# PS_DC-DC_15V_24V.net
KiCad netlist of a schematic drawn in Altium Designer
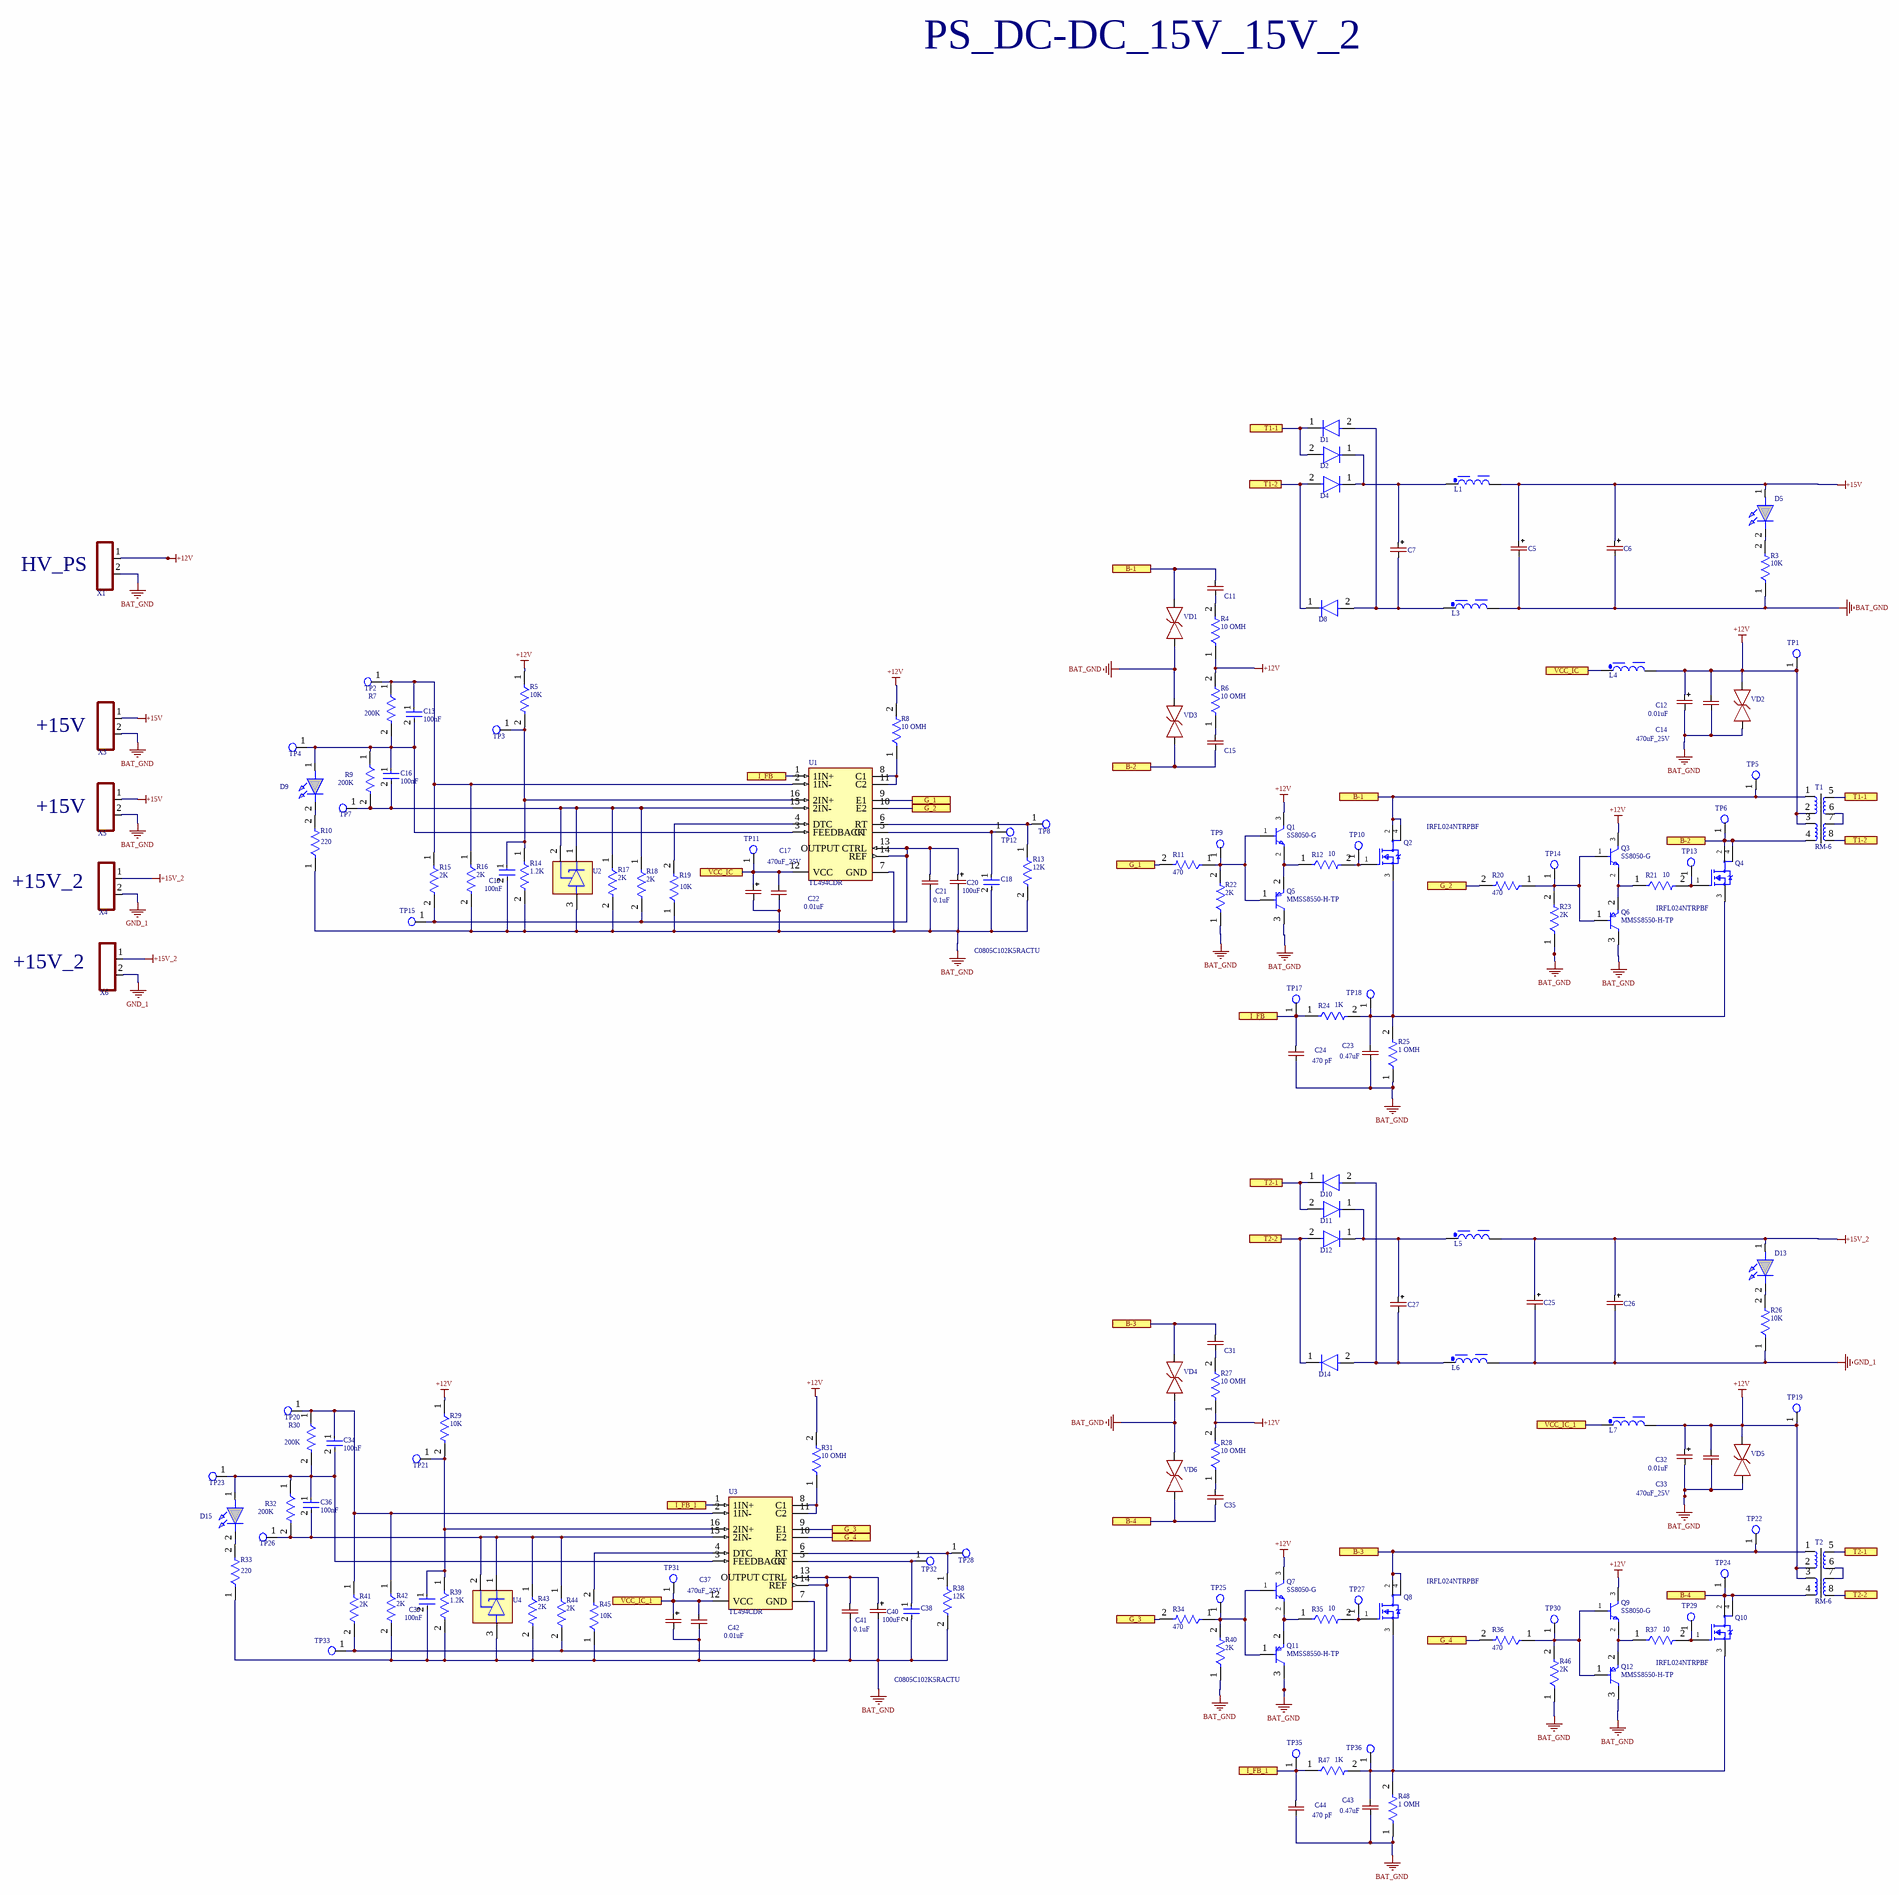
[diagram p0: PS_DC-DC_15V_24V.SchDoc]

(export (version "E")
  (design (tool "Eeschema 10.0.6"))
  (components
    (comp (ref "C5")
      (value "CAP-POLAR")
      (footprint "CAP_SMD_Size_G")
      (libsource (lib "PASSIVE_COMPONENTS") (part "CAP-POLAR"))
    )
    (comp (ref "C6")
      (value "CAP-POLAR")
      (footprint "CAP_SMD_Size_G")
      (libsource (lib "PASSIVE_COMPONENTS") (part "CAP-POLAR"))
    )
    (comp (ref "C7")
      (value "CAP-POLAR")
      (footprint "CAP_SMD_Size_G")
      (libsource (lib "PASSIVE_COMPONENTS") (part "CAP-POLAR"))
    )
    (comp (ref "C11")
      (value "CAP-V")
      (footprint "CAP-V")
      (libsource (lib "PASSIVE_COMPONENTS") (part "CAP-V"))
    )
    (comp (ref "C12")
      (value "0.01uF")
      (footprint "CAP-0805")
      (libsource (lib "PASSIVE_COMPONENTS") (part "CAP-NON-POLAR"))
    )
    (comp (ref "C13")
      (value "100nF")
      (footprint "FP-C0805C-DN-MFG")
      (description "CAP CER 10000PF 50V X7R 0805")
      (fields
        (field (name "MANUFACTURER PART NUMBER") "C0805C103J5RACTU")
        (field (name "MANUFACTURER") "KEMET")
      )
      (libsource (lib "Altium Content Vault") (part "b4654b650e69147ec39a6b967a45e02"))
    )
    (comp (ref "C14")
      (value "470uF_25V")
      (footprint "CAP_SMD_Size_G")
      (libsource (lib "PASSIVE_COMPONENTS") (part "CAP-POLAR"))
    )
    (comp (ref "C15")
      (value "CAP-V")
      (footprint "CAP-V")
      (libsource (lib "PASSIVE_COMPONENTS") (part "CAP-V"))
    )
    (comp (ref "C16")
      (value "100nF")
      (footprint "FP-C0805C-DN-MFG")
      (description "CAP CER 10000PF 50V X7R 0805")
      (fields
        (field (name "MANUFACTURER PART NUMBER") "C0805C103J5RACTU")
        (field (name "MANUFACTURER") "KEMET")
      )
      (libsource (lib "Altium Content Vault") (part "b4654b650e69147ec39a6b967a45e02"))
    )
    (comp (ref "C17")
      (value "470uF_25V")
      (footprint "CAP_SMD_Size_G")
      (libsource (lib "PASSIVE_COMPONENTS") (part "CAP-POLAR"))
    )
    (comp (ref "C18")
      (value "C0805C102K5RACTU")
      (footprint "FP-C0805C-DN-MFG")
      (description "CAP CER 1000PF 50V X7R 0805")
      (fields
        (field (name "OCTOPART") "https://octopart.com/c0805c102k5ractu-kemet-93010")
        (field (name "TOLERANCE") "0.1")
      )
      (libsource (lib "Altium Content Vault") (part "b4654b650e69147ec39a6b967a45e02"))
    )
    (comp (ref "C19")
      (value "100nF")
      (footprint "FP-C0805C-DN-MFG")
      (description "CAP CER 10000PF 50V X7R 0805")
      (fields
        (field (name "MANUFACTURER PART NUMBER") "C0805C103J5RACTU")
        (field (name "MANUFACTURER") "KEMET")
      )
      (libsource (lib "Altium Content Vault") (part "b4654b650e69147ec39a6b967a45e02"))
    )
    (comp (ref "C20")
      (value "100uF")
      (footprint "CAP-TAN-D")
      (libsource (lib "PASSIVE_COMPONENTS") (part "CAP-POLAR"))
    )
    (comp (ref "C21")
      (value "0.1uF")
      (footprint "CAP-0805")
      (libsource (lib "PASSIVE_COMPONENTS") (part "CAP-NON-POLAR"))
    )
    (comp (ref "C22")
      (value "0.01uF")
      (footprint "CAP-0805")
      (libsource (lib "PASSIVE_COMPONENTS") (part "CAP-NON-POLAR"))
    )
    (comp (ref "C23")
      (value "0.47uF")
      (footprint "CAP-0805")
      (libsource (lib "PASSIVE_COMPONENTS") (part "CAP-NON-POLAR"))
    )
    (comp (ref "C24")
      (value "470 pF")
      (footprint "CAP-0805")
      (libsource (lib "PASSIVE_COMPONENTS") (part "CAP-NON-POLAR"))
    )
    (comp (ref "C25")
      (value "CAP-POLAR")
      (footprint "CAP_SMD_Size_G")
      (libsource (lib "PASSIVE_COMPONENTS") (part "CAP-POLAR"))
    )
    (comp (ref "C26")
      (value "CAP-POLAR")
      (footprint "CAP_SMD_Size_G")
      (libsource (lib "PASSIVE_COMPONENTS") (part "CAP-POLAR"))
    )
    (comp (ref "C27")
      (value "CAP-POLAR")
      (footprint "CAP_SMD_Size_G")
      (libsource (lib "PASSIVE_COMPONENTS") (part "CAP-POLAR"))
    )
    (comp (ref "C31")
      (value "CAP-V")
      (footprint "CAP-V")
      (libsource (lib "PASSIVE_COMPONENTS") (part "CAP-V"))
    )
    (comp (ref "C32")
      (value "0.01uF")
      (footprint "CAP-0805")
      (libsource (lib "PASSIVE_COMPONENTS") (part "CAP-NON-POLAR"))
    )
    (comp (ref "C33")
      (value "470uF_25V")
      (footprint "CAP_SMD_Size_G")
      (libsource (lib "PASSIVE_COMPONENTS") (part "CAP-POLAR"))
    )
    (comp (ref "C34")
      (value "100nF")
      (footprint "FP-C0805C-DN-MFG")
      (description "CAP CER 10000PF 50V X7R 0805")
      (fields
        (field (name "MANUFACTURER PART NUMBER") "C0805C103J5RACTU")
        (field (name "MANUFACTURER") "KEMET")
      )
      (libsource (lib "Altium Content Vault") (part "b4654b650e69147ec39a6b967a45e02"))
    )
    (comp (ref "C35")
      (value "CAP-V")
      (footprint "CAP-V")
      (libsource (lib "PASSIVE_COMPONENTS") (part "CAP-V"))
    )
    (comp (ref "C36")
      (value "100nF")
      (footprint "FP-C0805C-DN-MFG")
      (description "CAP CER 10000PF 50V X7R 0805")
      (fields
        (field (name "MANUFACTURER PART NUMBER") "C0805C103J5RACTU")
        (field (name "MANUFACTURER") "KEMET")
      )
      (libsource (lib "Altium Content Vault") (part "b4654b650e69147ec39a6b967a45e02"))
    )
    (comp (ref "C37")
      (value "470uF_25V")
      (footprint "CAP_SMD_Size_G")
      (libsource (lib "PASSIVE_COMPONENTS") (part "CAP-POLAR"))
    )
    (comp (ref "C38")
      (value "C0805C102K5RACTU")
      (footprint "FP-C0805C-DN-MFG")
      (description "CAP CER 1000PF 50V X7R 0805")
      (fields
        (field (name "OCTOPART") "https://octopart.com/c0805c102k5ractu-kemet-93010")
        (field (name "TOLERANCE") "0.1")
      )
      (libsource (lib "Altium Content Vault") (part "b4654b650e69147ec39a6b967a45e02"))
    )
    (comp (ref "C39")
      (value "100nF")
      (footprint "FP-C0805C-DN-MFG")
      (description "CAP CER 10000PF 50V X7R 0805")
      (fields
        (field (name "MANUFACTURER PART NUMBER") "C0805C103J5RACTU")
        (field (name "MANUFACTURER") "KEMET")
      )
      (libsource (lib "Altium Content Vault") (part "b4654b650e69147ec39a6b967a45e02"))
    )
    (comp (ref "C40")
      (value "100uF")
      (footprint "CAP-TAN-D")
      (libsource (lib "PASSIVE_COMPONENTS") (part "CAP-POLAR"))
    )
    (comp (ref "C41")
      (value "0.1uF")
      (footprint "CAP-0805")
      (libsource (lib "PASSIVE_COMPONENTS") (part "CAP-NON-POLAR"))
    )
    (comp (ref "C42")
      (value "0.01uF")
      (footprint "CAP-0805")
      (libsource (lib "PASSIVE_COMPONENTS") (part "CAP-NON-POLAR"))
    )
    (comp (ref "C43")
      (value "0.47uF")
      (footprint "CAP-0805")
      (libsource (lib "PASSIVE_COMPONENTS") (part "CAP-NON-POLAR"))
    )
    (comp (ref "C44")
      (value "470 pF")
      (footprint "CAP-0805")
      (libsource (lib "PASSIVE_COMPONENTS") (part "CAP-NON-POLAR"))
    )
    (comp (ref "D1") (value "US1G") (footprint "DO-214AA") (libsource (lib "Diodes") (part "US1G")))
    (comp (ref "D2") (value "US1G") (footprint "DO-214AA") (libsource (lib "Diodes") (part "US1G")))
    (comp (ref "D4") (value "US1G") (footprint "DO-214AA") (libsource (lib "Diodes") (part "US1G")))
    (comp (ref "D5")
      (value "151031YS06000")
      (footprint "LED_RED")
      (description "WURTH ELEKTRONIK - 151031YS06000 - LED, Yellow, Through Hole, T-1 (3mm), 30 mA, 2 V, 590 nm")
      (fields (field (name "MOUSER PART NUMBER") "710-151031YS06000"))
      (libsource (lib "Optic-LED") (part "LED"))
    )
    (comp (ref "D8") (value "US1G") (footprint "DO-214AA") (libsource (lib "Diodes") (part "US1G")))
    (comp (ref "D9")
      (value "151031YS06000")
      (footprint "LED_RED")
      (description "WURTH ELEKTRONIK - 151031YS06000 - LED, Yellow, Through Hole, T-1 (3mm), 30 mA, 2 V, 590 nm")
      (fields (field (name "MOUSER PART NUMBER") "710-151031YS06000"))
      (libsource (lib "Optic-LED") (part "LED"))
    )
    (comp (ref "D10") (value "US1G") (footprint "DO-214AA") (libsource (lib "Diodes") (part "US1G")))
    (comp (ref "D11") (value "US1G") (footprint "DO-214AA") (libsource (lib "Diodes") (part "US1G")))
    (comp (ref "D12") (value "US1G") (footprint "DO-214AA") (libsource (lib "Diodes") (part "US1G")))
    (comp (ref "D13")
      (value "151031YS06000")
      (footprint "LED_RED")
      (description "WURTH ELEKTRONIK - 151031YS06000 - LED, Yellow, Through Hole, T-1 (3mm), 30 mA, 2 V, 590 nm")
      (fields (field (name "MOUSER PART NUMBER") "710-151031YS06000"))
      (libsource (lib "Optic-LED") (part "LED"))
    )
    (comp (ref "D14") (value "US1G") (footprint "DO-214AA") (libsource (lib "Diodes") (part "US1G")))
    (comp (ref "D15")
      (value "151031YS06000")
      (footprint "LED_RED")
      (description "WURTH ELEKTRONIK - 151031YS06000 - LED, Yellow, Through Hole, T-1 (3mm), 30 mA, 2 V, 590 nm")
      (fields (field (name "MOUSER PART NUMBER") "710-151031YS06000"))
      (libsource (lib "Optic-LED") (part "LED"))
    )
    (comp (ref "L1")
      (value "390µH, 0.38A")
      (footprint "WE-PD2_7850")
      (description "WE-PD2 SMT Power Inductor, size 7850, 390µH, 0.38A, 1.77Ω")
      (fields
        (field (name "MANUFACTURER PART NUMBER") "744775239")
        (field (name "MANUFACTURER") "Wurth Elektronik")
      )
      (libsource (lib "WE-PD2 (rev22d)") (part "744775239"))
    )
    (comp (ref "L3")
      (value "390µH, 0.38A")
      (footprint "WE-PD2_7850")
      (description "WE-PD2 SMT Power Inductor, size 7850, 390µH, 0.38A, 1.77Ω")
      (fields
        (field (name "MANUFACTURER PART NUMBER") "744775239")
        (field (name "MANUFACTURER") "Wurth Elektronik")
      )
      (libsource (lib "WE-PD2 (rev22d)") (part "744775239"))
    )
    (comp (ref "L4")
      (value "390µH, 0.38A")
      (footprint "WE-PD2_7850")
      (description "WE-PD2 SMT Power Inductor, size 7850, 390µH, 0.38A, 1.77Ω")
      (fields
        (field (name "MANUFACTURER PART NUMBER") "744775239")
        (field (name "MANUFACTURER") "Wurth Elektronik")
      )
      (libsource (lib "WE-PD2 (rev22d)") (part "744775239"))
    )
    (comp (ref "L5")
      (value "390µH, 0.38A")
      (footprint "WE-PD2_7850")
      (description "WE-PD2 SMT Power Inductor, size 7850, 390µH, 0.38A, 1.77Ω")
      (fields
        (field (name "MANUFACTURER PART NUMBER") "744775239")
        (field (name "MANUFACTURER") "Wurth Elektronik")
      )
      (libsource (lib "WE-PD2 (rev22d)") (part "744775239"))
    )
    (comp (ref "L6")
      (value "390µH, 0.38A")
      (footprint "WE-PD2_7850")
      (description "WE-PD2 SMT Power Inductor, size 7850, 390µH, 0.38A, 1.77Ω")
      (fields
        (field (name "MANUFACTURER PART NUMBER") "744775239")
        (field (name "MANUFACTURER") "Wurth Elektronik")
      )
      (libsource (lib "WE-PD2 (rev22d)") (part "744775239"))
    )
    (comp (ref "L7")
      (value "390µH, 0.38A")
      (footprint "WE-PD2_7850")
      (description "WE-PD2 SMT Power Inductor, size 7850, 390µH, 0.38A, 1.77Ω")
      (fields
        (field (name "MANUFACTURER PART NUMBER") "744775239")
        (field (name "MANUFACTURER") "Wurth Elektronik")
      )
      (libsource (lib "WE-PD2 (rev22d)") (part "744775239"))
    )
    (comp (ref "Q1")
      (value "SS8050-G")
      (footprint "FP-SS8050-G-MFG")
      (description "NPN TRANSISTOR 1.5A 40V SOT-23 R")
      (libsource (lib "Altium Content Vault") (part "2a1388f82443b098dcd57d24ac7632d"))
    )
    (comp (ref "Q2")
      (value "IRFL024NTRPBF")
      (footprint "FP-PG-SOT223-3-IPC_B")
      (description "MOSFET N-CH 55V 2.8A SOT223")
      (libsource (lib "Altium Content Vault") (part "7f70c8421781a2c4d0598199639518f"))
    )
    (comp (ref "Q3")
      (value "SS8050-G")
      (footprint "FP-SS8050-G-MFG")
      (description "NPN TRANSISTOR 1.5A 40V SOT-23 R")
      (libsource (lib "Altium Content Vault") (part "2a1388f82443b098dcd57d24ac7632d"))
    )
    (comp (ref "Q4")
      (value "IRFL024NTRPBF")
      (footprint "FP-PG-SOT223-3-IPC_B")
      (description "MOSFET N-CH 55V 2.8A SOT223")
      (libsource (lib "Altium Content Vault") (part "7f70c8421781a2c4d0598199639518f"))
    )
    (comp (ref "Q5")
      (value "MMSS8550-H-TP")
      (footprint "FP-SOT-23-IPC_B")
      (description "TRANS PNP 25V 1.5A SOT23")
      (libsource (lib "Altium Content Vault") (part "0e8486ed3b47d9c69b8404ba87cf0f7"))
    )
    (comp (ref "Q6")
      (value "MMSS8550-H-TP")
      (footprint "FP-SOT-23-IPC_B")
      (description "TRANS PNP 25V 1.5A SOT23")
      (libsource (lib "Altium Content Vault") (part "0e8486ed3b47d9c69b8404ba87cf0f7"))
    )
    (comp (ref "Q7")
      (value "SS8050-G")
      (footprint "FP-SS8050-G-MFG")
      (description "NPN TRANSISTOR 1.5A 40V SOT-23 R")
      (libsource (lib "Altium Content Vault") (part "2a1388f82443b098dcd57d24ac7632d"))
    )
    (comp (ref "Q8")
      (value "IRFL024NTRPBF")
      (footprint "FP-PG-SOT223-3-IPC_B")
      (description "MOSFET N-CH 55V 2.8A SOT223")
      (libsource (lib "Altium Content Vault") (part "7f70c8421781a2c4d0598199639518f"))
    )
    (comp (ref "Q9")
      (value "SS8050-G")
      (footprint "FP-SS8050-G-MFG")
      (description "NPN TRANSISTOR 1.5A 40V SOT-23 R")
      (libsource (lib "Altium Content Vault") (part "2a1388f82443b098dcd57d24ac7632d"))
    )
    (comp (ref "Q10")
      (value "IRFL024NTRPBF")
      (footprint "FP-PG-SOT223-3-IPC_B")
      (description "MOSFET N-CH 55V 2.8A SOT223")
      (libsource (lib "Altium Content Vault") (part "7f70c8421781a2c4d0598199639518f"))
    )
    (comp (ref "Q11")
      (value "MMSS8550-H-TP")
      (footprint "FP-SOT-23-IPC_B")
      (description "TRANS PNP 25V 1.5A SOT23")
      (libsource (lib "Altium Content Vault") (part "0e8486ed3b47d9c69b8404ba87cf0f7"))
    )
    (comp (ref "Q12")
      (value "MMSS8550-H-TP")
      (footprint "FP-SOT-23-IPC_B")
      (description "TRANS PNP 25V 1.5A SOT23")
      (libsource (lib "Altium Content Vault") (part "0e8486ed3b47d9c69b8404ba87cf0f7"))
    )
    (comp (ref "R3")
      (value "10K")
      (footprint "RES-0805")
      (libsource (lib "PASSIVE_COMPONENTS") (part "RES-CONST"))
    )
    (comp (ref "R4")
      (value "10 OMH")
      (footprint "RES-1206")
      (libsource (lib "PASSIVE_COMPONENTS") (part "RES-CONST"))
    )
    (comp (ref "R5")
      (value "10K")
      (footprint "FP-CRCW0805-e3-MFG")
      (description "RES Thick Film, 2kΩ, 1%, 0.125W, 100ppm/°C, 0805")
      (fields (field (name "TOLERANCE") "1%"))
      (libsource (lib "Pasive_components") (part "CMP-2001-04908-2"))
    )
    (comp (ref "R6")
      (value "10 OMH")
      (footprint "RES-1206")
      (libsource (lib "PASSIVE_COMPONENTS") (part "RES-CONST"))
    )
    (comp (ref "R7")
      (value "200K")
      (footprint "FP-CRCW0805-e3-MFG")
      (description "RES Thick Film, 2kΩ, 1%, 0.125W, 100ppm/°C, 0805")
      (fields (field (name "TOLERANCE") "1%"))
      (libsource (lib "Pasive_components") (part "CMP-2001-04908-2"))
    )
    (comp (ref "R8")
      (value "10 OMH")
      (footprint "RES-1206")
      (libsource (lib "PASSIVE_COMPONENTS") (part "RES-CONST"))
    )
    (comp (ref "R9")
      (value "200K")
      (footprint "FP-CRCW0805-e3-MFG")
      (description "RES Thick Film, 2kΩ, 1%, 0.125W, 100ppm/°C, 0805")
      (fields (field (name "TOLERANCE") "1%"))
      (libsource (lib "Pasive_components") (part "CMP-2001-04908-2"))
    )
    (comp (ref "R10")
      (value "220")
      (footprint "RES-0805")
      (libsource (lib "PASSIVE_COMPONENTS") (part "RES-CONST"))
    )
    (comp (ref "R11")
      (value "470")
      (footprint "RES-0805")
      (libsource (lib "PASSIVE_COMPONENTS") (part "RES-CONST"))
    )
    (comp (ref "R12")
      (value "10")
      (footprint "RES-0805")
      (libsource (lib "PASSIVE_COMPONENTS") (part "RES-CONST"))
    )
    (comp (ref "R13")
      (value "12K")
      (footprint "FP-CRCW0805-e3-MFG")
      (description "RES Thick Film, 12kΩ, 1%, 0.125W, 100ppm/°C, 0805")
      (fields (field (name "TOLERANCE") "1%"))
      (libsource (lib "Pasive_components") (part "CMP-2001-04908-2"))
    )
    (comp (ref "R14")
      (value "1.2K")
      (footprint "FP-CRCW0805-e3-MFG")
      (description "RES Thick Film, 2kΩ, 1%, 0.125W, 100ppm/°C, 0805")
      (fields (field (name "TOLERANCE") "1%"))
      (libsource (lib "Pasive_components") (part "CMP-2001-04908-2"))
    )
    (comp (ref "R15")
      (value "2K")
      (footprint "FP-CRCW0805-e3-MFG")
      (description "RES Thick Film, 2kΩ, 1%, 0.125W, 100ppm/°C, 0805")
      (fields (field (name "TOLERANCE") "1%"))
      (libsource (lib "Pasive_components") (part "CMP-2001-04908-2"))
    )
    (comp (ref "R16")
      (value "2K")
      (footprint "FP-CRCW0805-e3-MFG")
      (description "RES Thick Film, 82kΩ, 1%, 0.125W, 100ppm/°C, 0805")
      (fields (field (name "TOLERANCE") "1%"))
      (libsource (lib "Pasive_components") (part "CMP-2001-04908-2"))
    )
    (comp (ref "R17")
      (value "2K")
      (footprint "FP-CRCW0805-e3-MFG")
      (description "RES Thick Film, 2kΩ, 1%, 0.125W, 100ppm/°C, 0805")
      (fields (field (name "TOLERANCE") "1%"))
      (libsource (lib "Pasive_components") (part "CMP-2001-04908-2"))
    )
    (comp (ref "R18")
      (value "2K")
      (footprint "FP-CRCW0805-e3-MFG")
      (description "RES Thick Film, 2kΩ, 1%, 0.125W, 100ppm/°C, 0805")
      (fields (field (name "TOLERANCE") "1%"))
      (libsource (lib "Pasive_components") (part "CMP-2001-04908-2"))
    )
    (comp (ref "R19")
      (value "10K")
      (footprint "RES-0805")
      (libsource (lib "PASSIVE_COMPONENTS") (part "RES-CONST"))
    )
    (comp (ref "R20")
      (value "470")
      (footprint "RES-0805")
      (libsource (lib "PASSIVE_COMPONENTS") (part "RES-CONST"))
    )
    (comp (ref "R21")
      (value "10")
      (footprint "RES-0805")
      (libsource (lib "PASSIVE_COMPONENTS") (part "RES-CONST"))
    )
    (comp (ref "R22")
      (value "2K")
      (footprint "RES-0805")
      (libsource (lib "PASSIVE_COMPONENTS") (part "RES-CONST"))
    )
    (comp (ref "R23")
      (value "2K")
      (footprint "RES-0805")
      (libsource (lib "PASSIVE_COMPONENTS") (part "RES-CONST"))
    )
    (comp (ref "R24")
      (value "1K")
      (footprint "RES-0805")
      (libsource (lib "PASSIVE_COMPONENTS") (part "RES-CONST"))
    )
    (comp (ref "R25")
      (value "1 OMH")
      (footprint "RES-2512")
      (libsource (lib "PASSIVE_COMPONENTS") (part "RES-CONST"))
    )
    (comp (ref "R26")
      (value "10K")
      (footprint "RES-0805")
      (libsource (lib "PASSIVE_COMPONENTS") (part "RES-CONST"))
    )
    (comp (ref "R27")
      (value "10 OMH")
      (footprint "RES-1206")
      (libsource (lib "PASSIVE_COMPONENTS") (part "RES-CONST"))
    )
    (comp (ref "R28")
      (value "10 OMH")
      (footprint "RES-1206")
      (libsource (lib "PASSIVE_COMPONENTS") (part "RES-CONST"))
    )
    (comp (ref "R29")
      (value "10K")
      (footprint "FP-CRCW0805-e3-MFG")
      (description "RES Thick Film, 2kΩ, 1%, 0.125W, 100ppm/°C, 0805")
      (fields (field (name "TOLERANCE") "1%"))
      (libsource (lib "Pasive_components") (part "CMP-2001-04908-2"))
    )
    (comp (ref "R30")
      (value "200K")
      (footprint "FP-CRCW0805-e3-MFG")
      (description "RES Thick Film, 2kΩ, 1%, 0.125W, 100ppm/°C, 0805")
      (fields (field (name "TOLERANCE") "1%"))
      (libsource (lib "Pasive_components") (part "CMP-2001-04908-2"))
    )
    (comp (ref "R31")
      (value "10 OMH")
      (footprint "RES-1206")
      (libsource (lib "PASSIVE_COMPONENTS") (part "RES-CONST"))
    )
    (comp (ref "R32")
      (value "200K")
      (footprint "FP-CRCW0805-e3-MFG")
      (description "RES Thick Film, 2kΩ, 1%, 0.125W, 100ppm/°C, 0805")
      (fields (field (name "TOLERANCE") "1%"))
      (libsource (lib "Pasive_components") (part "CMP-2001-04908-2"))
    )
    (comp (ref "R33")
      (value "220")
      (footprint "RES-0805")
      (libsource (lib "PASSIVE_COMPONENTS") (part "RES-CONST"))
    )
    (comp (ref "R34")
      (value "470")
      (footprint "RES-0805")
      (libsource (lib "PASSIVE_COMPONENTS") (part "RES-CONST"))
    )
    (comp (ref "R35")
      (value "10")
      (footprint "RES-0805")
      (libsource (lib "PASSIVE_COMPONENTS") (part "RES-CONST"))
    )
    (comp (ref "R36")
      (value "470")
      (footprint "RES-0805")
      (libsource (lib "PASSIVE_COMPONENTS") (part "RES-CONST"))
    )
    (comp (ref "R37")
      (value "10")
      (footprint "RES-0805")
      (libsource (lib "PASSIVE_COMPONENTS") (part "RES-CONST"))
    )
    (comp (ref "R38")
      (value "12K")
      (footprint "FP-CRCW0805-e3-MFG")
      (description "RES Thick Film, 12kΩ, 1%, 0.125W, 100ppm/°C, 0805")
      (fields (field (name "TOLERANCE") "1%"))
      (libsource (lib "Pasive_components") (part "CMP-2001-04908-2"))
    )
    (comp (ref "R39")
      (value "1.2K")
      (footprint "FP-CRCW0805-e3-MFG")
      (description "RES Thick Film, 2kΩ, 1%, 0.125W, 100ppm/°C, 0805")
      (fields (field (name "TOLERANCE") "1%"))
      (libsource (lib "Pasive_components") (part "CMP-2001-04908-2"))
    )
    (comp (ref "R40")
      (value "2K")
      (footprint "RES-0805")
      (libsource (lib "PASSIVE_COMPONENTS") (part "RES-CONST"))
    )
    (comp (ref "R41")
      (value "2K")
      (footprint "FP-CRCW0805-e3-MFG")
      (description "RES Thick Film, 2kΩ, 1%, 0.125W, 100ppm/°C, 0805")
      (fields (field (name "TOLERANCE") "1%"))
      (libsource (lib "Pasive_components") (part "CMP-2001-04908-2"))
    )
    (comp (ref "R42")
      (value "2K")
      (footprint "FP-CRCW0805-e3-MFG")
      (description "RES Thick Film, 82kΩ, 1%, 0.125W, 100ppm/°C, 0805")
      (fields (field (name "TOLERANCE") "1%"))
      (libsource (lib "Pasive_components") (part "CMP-2001-04908-2"))
    )
    (comp (ref "R43")
      (value "2K")
      (footprint "FP-CRCW0805-e3-MFG")
      (description "RES Thick Film, 2kΩ, 1%, 0.125W, 100ppm/°C, 0805")
      (fields (field (name "TOLERANCE") "1%"))
      (libsource (lib "Pasive_components") (part "CMP-2001-04908-2"))
    )
    (comp (ref "R44")
      (value "2K")
      (footprint "FP-CRCW0805-e3-MFG")
      (description "RES Thick Film, 2kΩ, 1%, 0.125W, 100ppm/°C, 0805")
      (fields (field (name "TOLERANCE") "1%"))
      (libsource (lib "Pasive_components") (part "CMP-2001-04908-2"))
    )
    (comp (ref "R45")
      (value "10K")
      (footprint "RES-0805")
      (libsource (lib "PASSIVE_COMPONENTS") (part "RES-CONST"))
    )
    (comp (ref "R46")
      (value "2K")
      (footprint "RES-0805")
      (libsource (lib "PASSIVE_COMPONENTS") (part "RES-CONST"))
    )
    (comp (ref "R47")
      (value "1K")
      (footprint "RES-0805")
      (libsource (lib "PASSIVE_COMPONENTS") (part "RES-CONST"))
    )
    (comp (ref "R48")
      (value "1 OMH")
      (footprint "RES-2512")
      (libsource (lib "PASSIVE_COMPONENTS") (part "RES-CONST"))
    )
    (comp (ref "T1")
      (value "RM-6")
      (footprint "TRANS_RM6")
      (libsource (lib "Transformers") (part "RM_6_12-12-18-18"))
    )
    (comp (ref "T2")
      (value "RM-6")
      (footprint "TRANS_RM6")
      (libsource (lib "Transformers") (part "RM_6_12-12-18-18"))
    )
    (comp (ref "TP1")
      (value "~")
      (footprint "Test_Point")
      (description "Test_Point")
      (libsource (lib "Connectors") (part "TP_PCB?"))
    )
    (comp (ref "TP2")
      (value "Test_Point_PCB")
      (footprint "Test_Point")
      (description "Test_Point")
      (libsource (lib "Test_Point") (part "TP_PCB?"))
    )
    (comp (ref "TP3")
      (value "Test_Point_PCB")
      (footprint "Test_Point")
      (description "Test_Point")
      (libsource (lib "Test_Point") (part "TP_PCB?"))
    )
    (comp (ref "TP4")
      (value "Test_Point_PCB")
      (footprint "Test_Point")
      (description "Test_Point")
      (libsource (lib "Test_Point") (part "TP_PCB?"))
    )
    (comp (ref "TP5")
      (value "~")
      (footprint "Test_Point")
      (description "Test_Point")
      (libsource (lib "Connectors") (part "TP_PCB?"))
    )
    (comp (ref "TP6")
      (value "~")
      (footprint "Test_Point")
      (description "Test_Point")
      (libsource (lib "Connectors") (part "TP_PCB?"))
    )
    (comp (ref "TP7")
      (value "~")
      (footprint "Test_Point")
      (description "Test_Point")
      (libsource (lib "Connectors") (part "TP_PCB?"))
    )
    (comp (ref "TP8")
      (value "~")
      (footprint "Test_Point")
      (description "Test_Point")
      (libsource (lib "Connectors") (part "TP_PCB?"))
    )
    (comp (ref "TP9")
      (value "~")
      (footprint "Test_Point")
      (description "Test_Point")
      (libsource (lib "Connectors") (part "TP_PCB?"))
    )
    (comp (ref "TP10")
      (value "~")
      (footprint "Test_Point")
      (description "Test_Point")
      (libsource (lib "Connectors") (part "TP_PCB?"))
    )
    (comp (ref "TP11")
      (value "~")
      (footprint "Test_Point")
      (description "Test_Point")
      (libsource (lib "Connectors") (part "TP_PCB?"))
    )
    (comp (ref "TP12")
      (value "Test_Point_PCB")
      (footprint "Test_Point")
      (description "Test_Point")
      (libsource (lib "Test_Point") (part "TP_PCB?"))
    )
    (comp (ref "TP13")
      (value "~")
      (footprint "Test_Point")
      (description "Test_Point")
      (libsource (lib "Connectors") (part "TP_PCB?"))
    )
    (comp (ref "TP14")
      (value "~")
      (footprint "Test_Point")
      (description "Test_Point")
      (libsource (lib "Connectors") (part "TP_PCB?"))
    )
    (comp (ref "TP15")
      (value "Test_Point_PCB")
      (footprint "Test_Point")
      (description "Test_Point")
      (libsource (lib "Test_Point") (part "TP_PCB?"))
    )
    (comp (ref "TP17")
      (value "~")
      (footprint "Test_Point")
      (description "Test_Point")
      (libsource (lib "Connectors") (part "TP_PCB?"))
    )
    (comp (ref "TP18")
      (value "~")
      (footprint "Test_Point")
      (description "Test_Point")
      (libsource (lib "Connectors") (part "TP_PCB?"))
    )
    (comp (ref "TP19")
      (value "~")
      (footprint "Test_Point")
      (description "Test_Point")
      (libsource (lib "Connectors") (part "TP_PCB?"))
    )
    (comp (ref "TP20")
      (value "Test_Point_PCB")
      (footprint "Test_Point")
      (description "Test_Point")
      (libsource (lib "Test_Point") (part "TP_PCB?"))
    )
    (comp (ref "TP21")
      (value "Test_Point_PCB")
      (footprint "Test_Point")
      (description "Test_Point")
      (libsource (lib "Test_Point") (part "TP_PCB?"))
    )
    (comp (ref "TP22")
      (value "~")
      (footprint "Test_Point")
      (description "Test_Point")
      (libsource (lib "Connectors") (part "TP_PCB?"))
    )
    (comp (ref "TP23")
      (value "Test_Point_PCB")
      (footprint "Test_Point")
      (description "Test_Point")
      (libsource (lib "Test_Point") (part "TP_PCB?"))
    )
    (comp (ref "TP24")
      (value "~")
      (footprint "Test_Point")
      (description "Test_Point")
      (libsource (lib "Connectors") (part "TP_PCB?"))
    )
    (comp (ref "TP25")
      (value "~")
      (footprint "Test_Point")
      (description "Test_Point")
      (libsource (lib "Connectors") (part "TP_PCB?"))
    )
    (comp (ref "TP26")
      (value "~")
      (footprint "Test_Point")
      (description "Test_Point")
      (libsource (lib "Connectors") (part "TP_PCB?"))
    )
    (comp (ref "TP27")
      (value "~")
      (footprint "Test_Point")
      (description "Test_Point")
      (libsource (lib "Connectors") (part "TP_PCB?"))
    )
    (comp (ref "TP28")
      (value "~")
      (footprint "Test_Point")
      (description "Test_Point")
      (libsource (lib "Connectors") (part "TP_PCB?"))
    )
    (comp (ref "TP29")
      (value "~")
      (footprint "Test_Point")
      (description "Test_Point")
      (libsource (lib "Connectors") (part "TP_PCB?"))
    )
    (comp (ref "TP30")
      (value "~")
      (footprint "Test_Point")
      (description "Test_Point")
      (libsource (lib "Connectors") (part "TP_PCB?"))
    )
    (comp (ref "TP31")
      (value "~")
      (footprint "Test_Point")
      (description "Test_Point")
      (libsource (lib "Connectors") (part "TP_PCB?"))
    )
    (comp (ref "TP32")
      (value "Test_Point_PCB")
      (footprint "Test_Point")
      (description "Test_Point")
      (libsource (lib "Test_Point") (part "TP_PCB?"))
    )
    (comp (ref "TP33")
      (value "Test_Point_PCB")
      (footprint "Test_Point")
      (description "Test_Point")
      (libsource (lib "Test_Point") (part "TP_PCB?"))
    )
    (comp (ref "TP35")
      (value "~")
      (footprint "Test_Point")
      (description "Test_Point")
      (libsource (lib "Connectors") (part "TP_PCB?"))
    )
    (comp (ref "TP36")
      (value "~")
      (footprint "Test_Point")
      (description "Test_Point")
      (libsource (lib "Connectors") (part "TP_PCB?"))
    )
    (comp (ref "U1")
      (value "TL494CDR")
      (footprint "D0016A_N")
      (fields (field (name "MANUFACTURER") "Texas Instruments"))
      (libsource (lib "Altium Content Vault") (part "TI-494D16"))
    )
    (comp (ref "U2")
      (value "TL431")
      (footprint "TL431_SOT-23-3(A)")
      (description "TL431_SOT-23-3")
      (libsource (lib "Diodes") (part "TL431_SOT-23-3"))
    )
    (comp (ref "U3")
      (value "TL494CDR")
      (footprint "D0016A_N")
      (fields (field (name "MANUFACTURER") "Texas Instruments"))
      (libsource (lib "Altium Content Vault") (part "TI-494D16"))
    )
    (comp (ref "U4")
      (value "TL431")
      (footprint "TL431_SOT-23-3(A)")
      (description "TL431_SOT-23-3")
      (libsource (lib "Diodes") (part "TL431_SOT-23-3"))
    )
    (comp (ref "VD1")
      (value "Suppressor")
      (footprint "P6KE350CA")
      (libsource (lib "Diodes") (part "Suppressor"))
    )
    (comp (ref "VD2")
      (value "Suppressor")
      (footprint "DO-214AA")
      (libsource (lib "Diodes") (part "Suppressor"))
    )
    (comp (ref "VD3")
      (value "Suppressor")
      (footprint "P6KE350CA")
      (libsource (lib "Diodes") (part "Suppressor"))
    )
    (comp (ref "VD4")
      (value "Suppressor")
      (footprint "P6KE350CA")
      (libsource (lib "Diodes") (part "Suppressor"))
    )
    (comp (ref "VD5")
      (value "Suppressor")
      (footprint "DO-214AA")
      (libsource (lib "Diodes") (part "Suppressor"))
    )
    (comp (ref "VD6")
      (value "Suppressor")
      (footprint "P6KE350CA")
      (libsource (lib "Diodes") (part "Suppressor"))
    )
    (comp (ref "X1") (value "CONN-2-PIN") (footprint "XH2-") (libsource (lib "XH 2PIN") (part "CONN-2-PIN")))
    (comp (ref "X3") (value "CONN-2-PIN") (footprint "XH2-") (libsource (lib "XH 2PIN") (part "CONN-2-PIN")))
    (comp (ref "X4") (value "CONN-2-PIN") (footprint "XH2-") (libsource (lib "XH 2PIN") (part "CONN-2-PIN")))
    (comp (ref "X5") (value "CONN-2-PIN") (footprint "XH2-") (libsource (lib "XH 2PIN") (part "CONN-2-PIN")))
    (comp (ref "X6") (value "CONN-2-PIN") (footprint "XH2-") (libsource (lib "XH 2PIN") (part "CONN-2-PIN")))
  )
  (nets
    (net (code "1") (name "+12V") (class "Default")
      (node (ref "C12") (pin "2") (pinfunction "2_2") (pintype "passive"))
      (node (ref "C14") (pin "1") (pinfunction "+_1") (pintype "passive"))
      (node (ref "C32") (pin "2") (pinfunction "2_2") (pintype "passive"))
      (node (ref "C33") (pin "1") (pinfunction "+_1") (pintype "passive"))
      (node (ref "L4") (pin "2") (pinfunction "2_2") (pintype "passive"))
      (node (ref "L7") (pin "2") (pinfunction "2_2") (pintype "passive"))
      (node (ref "Q1") (pin "3") (pinfunction "C_3") (pintype "passive"))
      (node (ref "Q3") (pin "3") (pinfunction "C_3") (pintype "passive"))
      (node (ref "Q7") (pin "3") (pinfunction "C_3") (pintype "passive"))
      (node (ref "Q9") (pin "3") (pinfunction "C_3") (pintype "passive"))
      (node (ref "R27") (pin "1") (pinfunction "1_1") (pintype "passive"))
      (node (ref "R28") (pin "2") (pinfunction "2_2") (pintype "passive"))
      (node (ref "R29") (pin "1") (pinfunction "1_1") (pintype "passive"))
      (node (ref "R31") (pin "2") (pinfunction "2_2") (pintype "passive"))
      (node (ref "R4") (pin "1") (pinfunction "1_1") (pintype "passive"))
      (node (ref "R5") (pin "1") (pinfunction "1_1") (pintype "passive"))
      (node (ref "R6") (pin "2") (pinfunction "2_2") (pintype "passive"))
      (node (ref "R8") (pin "2") (pinfunction "2_2") (pintype "passive"))
      (node (ref "T1") (pin "2") (pinfunction "2_2") (pintype "passive"))
      (node (ref "T1") (pin "3") (pinfunction "3_3") (pintype "passive"))
      (node (ref "T2") (pin "2") (pinfunction "2_2") (pintype "passive"))
      (node (ref "T2") (pin "3") (pinfunction "3_3") (pintype "passive"))
      (node (ref "TP1") (pin "1") (pinfunction "G9_1") (pintype "passive"))
      (node (ref "TP19") (pin "1") (pinfunction "G9_1") (pintype "passive"))
      (node (ref "VD2") (pin "2") (pinfunction "A_2") (pintype "passive"))
      (node (ref "VD5") (pin "2") (pinfunction "A_2") (pintype "passive"))
      (node (ref "X1") (pin "1") (pinfunction "1_1") (pintype "passive"))
    )
    (net (code "2") (name "+15V") (class "Default")
      (node (ref "C5") (pin "1") (pinfunction "+_1") (pintype "passive"))
      (node (ref "C6") (pin "1") (pinfunction "+_1") (pintype "passive"))
      (node (ref "D5") (pin "1") (pinfunction "A_1") (pintype "passive"))
      (node (ref "L1") (pin "2") (pinfunction "2_2") (pintype "passive"))
      (node (ref "X3") (pin "1") (pinfunction "1_1") (pintype "passive"))
      (node (ref "X5") (pin "1") (pinfunction "1_1") (pintype "passive"))
    )
    (net (code "3") (name "+15V_2") (class "Default")
      (node (ref "C25") (pin "1") (pinfunction "+_1") (pintype "passive"))
      (node (ref "C26") (pin "1") (pinfunction "+_1") (pintype "passive"))
      (node (ref "D13") (pin "1") (pinfunction "A_1") (pintype "passive"))
      (node (ref "L5") (pin "2") (pinfunction "2_2") (pintype "passive"))
      (node (ref "X4") (pin "1") (pinfunction "1_1") (pintype "passive"))
      (node (ref "X6") (pin "1") (pinfunction "1_1") (pintype "passive"))
    )
    (net (code "4") (name "/B-1") (class "Default")
      (node (ref "C11") (pin "2") (pinfunction "2_2") (pintype "passive"))
      (node (ref "Q2") (pin "2") (pinfunction "D_2") (pintype "passive"))
      (node (ref "Q2") (pin "4") (pinfunction "D_4") (pintype "passive"))
      (node (ref "T1") (pin "1") (pinfunction "1_1") (pintype "passive"))
      (node (ref "TP5") (pin "1") (pinfunction "G9_1") (pintype "passive"))
      (node (ref "VD1") (pin "2") (pinfunction "A_2") (pintype "passive"))
    )
    (net (code "5") (name "/B-2") (class "Default")
      (node (ref "C15") (pin "1") (pinfunction "1_1") (pintype "passive"))
      (node (ref "Q4") (pin "2") (pinfunction "D_2") (pintype "passive"))
      (node (ref "Q4") (pin "4") (pinfunction "D_4") (pintype "passive"))
      (node (ref "T1") (pin "4") (pinfunction "4_4") (pintype "passive"))
      (node (ref "TP6") (pin "1") (pinfunction "G9_1") (pintype "passive"))
      (node (ref "VD3") (pin "1") (pinfunction "C_1") (pintype "passive"))
    )
    (net (code "6") (name "/B-3") (class "Default")
      (node (ref "C31") (pin "2") (pinfunction "2_2") (pintype "passive"))
      (node (ref "Q8") (pin "2") (pinfunction "D_2") (pintype "passive"))
      (node (ref "Q8") (pin "4") (pinfunction "D_4") (pintype "passive"))
      (node (ref "T2") (pin "1") (pinfunction "1_1") (pintype "passive"))
      (node (ref "TP22") (pin "1") (pinfunction "G9_1") (pintype "passive"))
      (node (ref "VD4") (pin "2") (pinfunction "A_2") (pintype "passive"))
    )
    (net (code "7") (name "/B-4") (class "Default")
      (node (ref "C35") (pin "1") (pinfunction "1_1") (pintype "passive"))
      (node (ref "Q10") (pin "2") (pinfunction "D_2") (pintype "passive"))
      (node (ref "Q10") (pin "4") (pinfunction "D_4") (pintype "passive"))
      (node (ref "T2") (pin "4") (pinfunction "4_4") (pintype "passive"))
      (node (ref "TP24") (pin "1") (pinfunction "G9_1") (pintype "passive"))
      (node (ref "VD6") (pin "1") (pinfunction "C_1") (pintype "passive"))
    )
    (net (code "8") (name "/G_1") (class "Default")
      (node (ref "R11") (pin "2") (pinfunction "2_2") (pintype "passive"))
      (node (ref "U1") (pin "9") (pinfunction "E1_9") (pintype "passive"))
    )
    (net (code "9") (name "/G_2") (class "Default")
      (node (ref "R20") (pin "2") (pinfunction "2_2") (pintype "passive"))
      (node (ref "U1") (pin "10") (pinfunction "E2_10") (pintype "passive"))
    )
    (net (code "10") (name "/G_3") (class "Default")
      (node (ref "R34") (pin "2") (pinfunction "2_2") (pintype "passive"))
      (node (ref "U3") (pin "9") (pinfunction "E1_9") (pintype "passive"))
    )
    (net (code "11") (name "/G_4") (class "Default")
      (node (ref "R36") (pin "2") (pinfunction "2_2") (pintype "passive"))
      (node (ref "U3") (pin "10") (pinfunction "E2_10") (pintype "passive"))
    )
    (net (code "12") (name "/I_FB") (class "Default")
      (node (ref "C24") (pin "2") (pinfunction "2_2") (pintype "passive"))
      (node (ref "R24") (pin "1") (pinfunction "1_1") (pintype "passive"))
      (node (ref "TP17") (pin "1") (pinfunction "G9_1") (pintype "passive"))
      (node (ref "U1") (pin "1") (pinfunction "1IN+_1") (pintype "input"))
    )
    (net (code "13") (name "/I_FB_1") (class "Default")
      (node (ref "C44") (pin "2") (pinfunction "2_2") (pintype "passive"))
      (node (ref "R47") (pin "1") (pinfunction "1_1") (pintype "passive"))
      (node (ref "TP35") (pin "1") (pinfunction "G9_1") (pintype "passive"))
      (node (ref "U3") (pin "1") (pinfunction "1IN+_1") (pintype "input"))
    )
    (net (code "14") (name "/T1-1") (class "Default")
      (node (ref "D1") (pin "1") (pinfunction "C_1") (pintype "passive"))
      (node (ref "D2") (pin "2") (pinfunction "A_2") (pintype "passive"))
      (node (ref "T1") (pin "5") (pinfunction "5_5") (pintype "passive"))
    )
    (net (code "15") (name "/T1-2") (class "Default")
      (node (ref "D4") (pin "2") (pinfunction "A_2") (pintype "passive"))
      (node (ref "D8") (pin "1") (pinfunction "C_1") (pintype "passive"))
      (node (ref "T1") (pin "8") (pinfunction "8_8") (pintype "passive"))
    )
    (net (code "16") (name "/T2-1") (class "Default")
      (node (ref "D10") (pin "1") (pinfunction "C_1") (pintype "passive"))
      (node (ref "D11") (pin "2") (pinfunction "A_2") (pintype "passive"))
      (node (ref "T2") (pin "5") (pinfunction "5_5") (pintype "passive"))
    )
    (net (code "17") (name "/T2-2") (class "Default")
      (node (ref "D12") (pin "2") (pinfunction "A_2") (pintype "passive"))
      (node (ref "D14") (pin "1") (pinfunction "C_1") (pintype "passive"))
      (node (ref "T2") (pin "8") (pinfunction "8_8") (pintype "passive"))
    )
    (net (code "18") (name "/VCC_IC") (class "Default")
      (node (ref "C17") (pin "1") (pinfunction "+_1") (pintype "passive"))
      (node (ref "C22") (pin "2") (pinfunction "2_2") (pintype "passive"))
      (node (ref "L4") (pin "1") (pinfunction "1_1") (pintype "passive"))
      (node (ref "TP11") (pin "1") (pinfunction "G9_1") (pintype "passive"))
      (node (ref "U1") (pin "12") (pinfunction "VCC_12") (pintype "power_in"))
    )
    (net (code "19") (name "/VCC_IC_1") (class "Default")
      (node (ref "C37") (pin "1") (pinfunction "+_1") (pintype "passive"))
      (node (ref "C42") (pin "2") (pinfunction "2_2") (pintype "passive"))
      (node (ref "L7") (pin "1") (pinfunction "1_1") (pintype "passive"))
      (node (ref "TP31") (pin "1") (pinfunction "G9_1") (pintype "passive"))
      (node (ref "U3") (pin "12") (pinfunction "VCC_12") (pintype "power_in"))
    )
    (net (code "20") (name "BAT_GND") (class "Default")
      (node (ref "C12") (pin "1") (pinfunction "1_1") (pintype "passive"))
      (node (ref "C14") (pin "2") (pinfunction "-_2") (pintype "passive"))
      (node (ref "C17") (pin "2") (pinfunction "-_2") (pintype "passive"))
      (node (ref "C18") (pin "2") (pinfunction "2_2") (pintype "passive"))
      (node (ref "C19") (pin "2") (pinfunction "2_2") (pintype "passive"))
      (node (ref "C20") (pin "2") (pinfunction "-_2") (pintype "passive"))
      (node (ref "C21") (pin "1") (pinfunction "1_1") (pintype "passive"))
      (node (ref "C22") (pin "1") (pinfunction "1_1") (pintype "passive"))
      (node (ref "C23") (pin "1") (pinfunction "1_1") (pintype "passive"))
      (node (ref "C24") (pin "1") (pinfunction "1_1") (pintype "passive"))
      (node (ref "C32") (pin "1") (pinfunction "1_1") (pintype "passive"))
      (node (ref "C33") (pin "2") (pinfunction "-_2") (pintype "passive"))
      (node (ref "C37") (pin "2") (pinfunction "-_2") (pintype "passive"))
      (node (ref "C38") (pin "2") (pinfunction "2_2") (pintype "passive"))
      (node (ref "C39") (pin "2") (pinfunction "2_2") (pintype "passive"))
      (node (ref "C40") (pin "2") (pinfunction "-_2") (pintype "passive"))
      (node (ref "C41") (pin "1") (pinfunction "1_1") (pintype "passive"))
      (node (ref "C42") (pin "1") (pinfunction "1_1") (pintype "passive"))
      (node (ref "C43") (pin "1") (pinfunction "1_1") (pintype "passive"))
      (node (ref "C44") (pin "1") (pinfunction "1_1") (pintype "passive"))
      (node (ref "C5") (pin "2") (pinfunction "-_2") (pintype "passive"))
      (node (ref "C6") (pin "2") (pinfunction "-_2") (pintype "passive"))
      (node (ref "L3") (pin "2") (pinfunction "2_2") (pintype "passive"))
      (node (ref "Q11") (pin "3") (pinfunction "C_3") (pintype "passive"))
      (node (ref "Q12") (pin "3") (pinfunction "C_3") (pintype "passive"))
      (node (ref "Q5") (pin "3") (pinfunction "C_3") (pintype "passive"))
      (node (ref "Q6") (pin "3") (pinfunction "C_3") (pintype "passive"))
      (node (ref "R10") (pin "1") (pinfunction "1_1") (pintype "passive"))
      (node (ref "R13") (pin "2") (pinfunction "2_2") (pintype "passive"))
      (node (ref "R14") (pin "2") (pinfunction "2_2") (pintype "passive"))
      (node (ref "R16") (pin "2") (pinfunction "2_2") (pintype "passive"))
      (node (ref "R17") (pin "2") (pinfunction "2_2") (pintype "passive"))
      (node (ref "R19") (pin "1") (pinfunction "1_1") (pintype "passive"))
      (node (ref "R22") (pin "1") (pinfunction "1_1") (pintype "passive"))
      (node (ref "R23") (pin "1") (pinfunction "1_1") (pintype "passive"))
      (node (ref "R25") (pin "1") (pinfunction "1_1") (pintype "passive"))
      (node (ref "R3") (pin "1") (pinfunction "1_1") (pintype "passive"))
      (node (ref "R33") (pin "1") (pinfunction "1_1") (pintype "passive"))
      (node (ref "R38") (pin "2") (pinfunction "2_2") (pintype "passive"))
      (node (ref "R39") (pin "2") (pinfunction "2_2") (pintype "passive"))
      (node (ref "R40") (pin "1") (pinfunction "1_1") (pintype "passive"))
      (node (ref "R42") (pin "2") (pinfunction "2_2") (pintype "passive"))
      (node (ref "R43") (pin "2") (pinfunction "2_2") (pintype "passive"))
      (node (ref "R45") (pin "1") (pinfunction "1_1") (pintype "passive"))
      (node (ref "R46") (pin "1") (pinfunction "1_1") (pintype "passive"))
      (node (ref "R48") (pin "1") (pinfunction "1_1") (pintype "passive"))
      (node (ref "U1") (pin "7") (pinfunction "GND_7") (pintype "power_in"))
      (node (ref "U2") (pin "3") (pinfunction "A_3") (pintype "passive"))
      (node (ref "U3") (pin "7") (pinfunction "GND_7") (pintype "power_in"))
      (node (ref "U4") (pin "3") (pinfunction "A_3") (pintype "passive"))
      (node (ref "VD1") (pin "1") (pinfunction "C_1") (pintype "passive"))
      (node (ref "VD2") (pin "1") (pinfunction "C_1") (pintype "passive"))
      (node (ref "VD3") (pin "2") (pinfunction "A_2") (pintype "passive"))
      (node (ref "VD4") (pin "1") (pinfunction "C_1") (pintype "passive"))
      (node (ref "VD5") (pin "1") (pinfunction "C_1") (pintype "passive"))
      (node (ref "VD6") (pin "2") (pinfunction "A_2") (pintype "passive"))
      (node (ref "X1") (pin "2") (pinfunction "2_2") (pintype "passive"))
      (node (ref "X3") (pin "2") (pinfunction "2_2") (pintype "passive"))
      (node (ref "X5") (pin "2") (pinfunction "2_2") (pintype "passive"))
    )
    (net (code "21") (name "GND_1") (class "Default")
      (node (ref "C25") (pin "2") (pinfunction "-_2") (pintype "passive"))
      (node (ref "C26") (pin "2") (pinfunction "-_2") (pintype "passive"))
      (node (ref "L6") (pin "2") (pinfunction "2_2") (pintype "passive"))
      (node (ref "R26") (pin "1") (pinfunction "1_1") (pintype "passive"))
      (node (ref "X4") (pin "2") (pinfunction "2_2") (pintype "passive"))
      (node (ref "X6") (pin "2") (pinfunction "2_2") (pintype "passive"))
    )
    (net (code "22") (name "Net-(C7-+)") (class "Default")
      (node (ref "C7") (pin "1") (pinfunction "+_1") (pintype "passive"))
      (node (ref "D2") (pin "1") (pinfunction "C_1") (pintype "passive"))
      (node (ref "D4") (pin "1") (pinfunction "C_1") (pintype "passive"))
      (node (ref "L1") (pin "1") (pinfunction "1_1") (pintype "passive"))
    )
    (net (code "23") (name "Net-(C7--)") (class "Default")
      (node (ref "C7") (pin "2") (pinfunction "-_2") (pintype "passive"))
      (node (ref "D1") (pin "2") (pinfunction "A_2") (pintype "passive"))
      (node (ref "D8") (pin "2") (pinfunction "A_2") (pintype "passive"))
      (node (ref "L3") (pin "1") (pinfunction "1_1") (pintype "passive"))
    )
    (net (code "24") (name "Net-(C11-Pad1)") (class "Default")
      (node (ref "C11") (pin "1") (pinfunction "1_1") (pintype "passive"))
      (node (ref "R4") (pin "2") (pinfunction "2_2") (pintype "passive"))
    )
    (net (code "25") (name "Net-(C15-Pad2)") (class "Default")
      (node (ref "C15") (pin "2") (pinfunction "2_2") (pintype "passive"))
      (node (ref "R6") (pin "1") (pinfunction "1_1") (pintype "passive"))
    )
    (net (code "26") (name "Net-(C20-+)") (class "Default")
      (node (ref "C20") (pin "1") (pinfunction "+_1") (pintype "passive"))
      (node (ref "C21") (pin "2") (pinfunction "2_2") (pintype "passive"))
      (node (ref "R15") (pin "2") (pinfunction "2_2") (pintype "passive"))
      (node (ref "R18") (pin "2") (pinfunction "2_2") (pintype "passive"))
      (node (ref "TP15") (pin "1") (pinfunction "G9_1") (pintype "passive"))
      (node (ref "U1") (pin "13") (pinfunction "OUTPUT_CTRL_13") (pintype "input"))
      (node (ref "U1") (pin "14") (pinfunction "REF_14") (pintype "output"))
    )
    (net (code "27") (name "Net-(C27-+)") (class "Default")
      (node (ref "C27") (pin "1") (pinfunction "+_1") (pintype "passive"))
      (node (ref "D11") (pin "1") (pinfunction "C_1") (pintype "passive"))
      (node (ref "D12") (pin "1") (pinfunction "C_1") (pintype "passive"))
      (node (ref "L5") (pin "1") (pinfunction "1_1") (pintype "passive"))
    )
    (net (code "28") (name "Net-(C27--)") (class "Default")
      (node (ref "C27") (pin "2") (pinfunction "-_2") (pintype "passive"))
      (node (ref "D10") (pin "2") (pinfunction "A_2") (pintype "passive"))
      (node (ref "D14") (pin "2") (pinfunction "A_2") (pintype "passive"))
      (node (ref "L6") (pin "1") (pinfunction "1_1") (pintype "passive"))
    )
    (net (code "29") (name "Net-(C31-Pad1)") (class "Default")
      (node (ref "C31") (pin "1") (pinfunction "1_1") (pintype "passive"))
      (node (ref "R27") (pin "2") (pinfunction "2_2") (pintype "passive"))
    )
    (net (code "30") (name "Net-(C35-Pad2)") (class "Default")
      (node (ref "C35") (pin "2") (pinfunction "2_2") (pintype "passive"))
      (node (ref "R28") (pin "1") (pinfunction "1_1") (pintype "passive"))
    )
    (net (code "31") (name "Net-(C40-+)") (class "Default")
      (node (ref "C40") (pin "1") (pinfunction "+_1") (pintype "passive"))
      (node (ref "C41") (pin "2") (pinfunction "2_2") (pintype "passive"))
      (node (ref "R41") (pin "2") (pinfunction "2_2") (pintype "passive"))
      (node (ref "R44") (pin "2") (pinfunction "2_2") (pintype "passive"))
      (node (ref "TP33") (pin "1") (pinfunction "G9_1") (pintype "passive"))
      (node (ref "U3") (pin "13") (pinfunction "OUTPUT_CTRL_13") (pintype "input"))
      (node (ref "U3") (pin "14") (pinfunction "REF_14") (pintype "output"))
    )
    (net (code "32") (name "Net-(D5-K)") (class "Default")
      (node (ref "D5") (pin "2") (pinfunction "K_2") (pintype "passive"))
      (node (ref "R3") (pin "2") (pinfunction "2_2") (pintype "passive"))
    )
    (net (code "33") (name "Net-(D9-A)") (class "Default")
      (node (ref "C13") (pin "2") (pinfunction "2_2") (pintype "passive"))
      (node (ref "C16") (pin "1") (pinfunction "1_1") (pintype "passive"))
      (node (ref "D9") (pin "1") (pinfunction "A_1") (pintype "passive"))
      (node (ref "R7") (pin "2") (pinfunction "2_2") (pintype "passive"))
      (node (ref "R9") (pin "1") (pinfunction "1_1") (pintype "passive"))
      (node (ref "TP4") (pin "1") (pinfunction "G9_1") (pintype "passive"))
      (node (ref "U1") (pin "3") (pinfunction "FEEDBACK_3") (pintype "input"))
    )
    (net (code "34") (name "Net-(D9-K)") (class "Default")
      (node (ref "D9") (pin "2") (pinfunction "K_2") (pintype "passive"))
      (node (ref "R10") (pin "2") (pinfunction "2_2") (pintype "passive"))
    )
    (net (code "35") (name "Net-(D13-K)") (class "Default")
      (node (ref "D13") (pin "2") (pinfunction "K_2") (pintype "passive"))
      (node (ref "R26") (pin "2") (pinfunction "2_2") (pintype "passive"))
    )
    (net (code "36") (name "Net-(D15-A)") (class "Default")
      (node (ref "C34") (pin "2") (pinfunction "2_2") (pintype "passive"))
      (node (ref "C36") (pin "1") (pinfunction "1_1") (pintype "passive"))
      (node (ref "D15") (pin "1") (pinfunction "A_1") (pintype "passive"))
      (node (ref "R30") (pin "2") (pinfunction "2_2") (pintype "passive"))
      (node (ref "R32") (pin "1") (pinfunction "1_1") (pintype "passive"))
      (node (ref "TP23") (pin "1") (pinfunction "G9_1") (pintype "passive"))
      (node (ref "U3") (pin "3") (pinfunction "FEEDBACK_3") (pintype "input"))
    )
    (net (code "37") (name "Net-(D15-K)") (class "Default")
      (node (ref "D15") (pin "2") (pinfunction "K_2") (pintype "passive"))
      (node (ref "R33") (pin "2") (pinfunction "2_2") (pintype "passive"))
    )
    (net (code "38") (name "Net-(Q1-B)") (class "Default")
      (node (ref "Q1") (pin "1") (pinfunction "B_1") (pintype "passive"))
      (node (ref "Q5") (pin "1") (pinfunction "B_1") (pintype "passive"))
      (node (ref "R11") (pin "1") (pinfunction "1_1") (pintype "passive"))
      (node (ref "R22") (pin "2") (pinfunction "2_2") (pintype "passive"))
      (node (ref "TP9") (pin "1") (pinfunction "G9_1") (pintype "passive"))
    )
    (net (code "39") (name "Net-(Q1-E)") (class "Default")
      (node (ref "Q1") (pin "2") (pinfunction "E_2") (pintype "passive"))
      (node (ref "Q5") (pin "2") (pinfunction "E_2") (pintype "passive"))
      (node (ref "R12") (pin "1") (pinfunction "1_1") (pintype "passive"))
    )
    (net (code "40") (name "Net-(Q2-G)") (class "Default")
      (node (ref "Q2") (pin "1") (pinfunction "G_1") (pintype "passive"))
      (node (ref "R12") (pin "2") (pinfunction "2_2") (pintype "passive"))
      (node (ref "TP10") (pin "1") (pinfunction "G9_1") (pintype "passive"))
    )
    (net (code "41") (name "Net-(Q2-S)") (class "Default")
      (node (ref "C23") (pin "2") (pinfunction "2_2") (pintype "passive"))
      (node (ref "Q2") (pin "3") (pinfunction "S_3") (pintype "passive"))
      (node (ref "Q4") (pin "3") (pinfunction "S_3") (pintype "passive"))
      (node (ref "R24") (pin "2") (pinfunction "2_2") (pintype "passive"))
      (node (ref "R25") (pin "2") (pinfunction "2_2") (pintype "passive"))
      (node (ref "TP18") (pin "1") (pinfunction "G9_1") (pintype "passive"))
    )
    (net (code "42") (name "Net-(Q3-B)") (class "Default")
      (node (ref "Q3") (pin "1") (pinfunction "B_1") (pintype "passive"))
      (node (ref "Q6") (pin "1") (pinfunction "B_1") (pintype "passive"))
      (node (ref "R20") (pin "1") (pinfunction "1_1") (pintype "passive"))
      (node (ref "R23") (pin "2") (pinfunction "2_2") (pintype "passive"))
      (node (ref "TP14") (pin "1") (pinfunction "G9_1") (pintype "passive"))
    )
    (net (code "43") (name "Net-(Q3-E)") (class "Default")
      (node (ref "Q3") (pin "2") (pinfunction "E_2") (pintype "passive"))
      (node (ref "Q6") (pin "2") (pinfunction "E_2") (pintype "passive"))
      (node (ref "R21") (pin "1") (pinfunction "1_1") (pintype "passive"))
    )
    (net (code "44") (name "Net-(Q4-G)") (class "Default")
      (node (ref "Q4") (pin "1") (pinfunction "G_1") (pintype "passive"))
      (node (ref "R21") (pin "2") (pinfunction "2_2") (pintype "passive"))
      (node (ref "TP13") (pin "1") (pinfunction "G9_1") (pintype "passive"))
    )
    (net (code "45") (name "Net-(Q8-G)") (class "Default")
      (node (ref "Q8") (pin "1") (pinfunction "G_1") (pintype "passive"))
      (node (ref "R35") (pin "2") (pinfunction "2_2") (pintype "passive"))
      (node (ref "TP27") (pin "1") (pinfunction "G9_1") (pintype "passive"))
    )
    (net (code "46") (name "Net-(Q10-G)") (class "Default")
      (node (ref "Q10") (pin "1") (pinfunction "G_1") (pintype "passive"))
      (node (ref "R37") (pin "2") (pinfunction "2_2") (pintype "passive"))
      (node (ref "TP29") (pin "1") (pinfunction "G9_1") (pintype "passive"))
    )
    (net (code "47") (name "Net-(Q10-S)") (class "Default")
      (node (ref "C43") (pin "2") (pinfunction "2_2") (pintype "passive"))
      (node (ref "Q10") (pin "3") (pinfunction "S_3") (pintype "passive"))
      (node (ref "Q8") (pin "3") (pinfunction "S_3") (pintype "passive"))
      (node (ref "R47") (pin "2") (pinfunction "2_2") (pintype "passive"))
      (node (ref "R48") (pin "2") (pinfunction "2_2") (pintype "passive"))
      (node (ref "TP36") (pin "1") (pinfunction "G9_1") (pintype "passive"))
    )
    (net (code "48") (name "Net-(Q11-B)") (class "Default")
      (node (ref "Q11") (pin "1") (pinfunction "B_1") (pintype "passive"))
      (node (ref "Q7") (pin "1") (pinfunction "B_1") (pintype "passive"))
      (node (ref "R34") (pin "1") (pinfunction "1_1") (pintype "passive"))
      (node (ref "R40") (pin "2") (pinfunction "2_2") (pintype "passive"))
      (node (ref "TP25") (pin "1") (pinfunction "G9_1") (pintype "passive"))
    )
    (net (code "49") (name "Net-(Q11-E)") (class "Default")
      (node (ref "Q11") (pin "2") (pinfunction "E_2") (pintype "passive"))
      (node (ref "Q7") (pin "2") (pinfunction "E_2") (pintype "passive"))
      (node (ref "R35") (pin "1") (pinfunction "1_1") (pintype "passive"))
    )
    (net (code "50") (name "Net-(Q12-B)") (class "Default")
      (node (ref "Q12") (pin "1") (pinfunction "B_1") (pintype "passive"))
      (node (ref "Q9") (pin "1") (pinfunction "B_1") (pintype "passive"))
      (node (ref "R36") (pin "1") (pinfunction "1_1") (pintype "passive"))
      (node (ref "R46") (pin "2") (pinfunction "2_2") (pintype "passive"))
      (node (ref "TP30") (pin "1") (pinfunction "G9_1") (pintype "passive"))
    )
    (net (code "51") (name "Net-(Q12-E)") (class "Default")
      (node (ref "Q12") (pin "2") (pinfunction "E_2") (pintype "passive"))
      (node (ref "Q9") (pin "2") (pinfunction "E_2") (pintype "passive"))
      (node (ref "R37") (pin "1") (pinfunction "1_1") (pintype "passive"))
    )
    (net (code "52") (name "Net-(T1-Pad6)") (class "Default")
      (node (ref "T1") (pin "6") (pinfunction "6_6") (pintype "passive"))
      (node (ref "T1") (pin "7") (pinfunction "7_7") (pintype "passive"))
    )
    (net (code "53") (name "Net-(T2-Pad6)") (class "Default")
      (node (ref "T2") (pin "6") (pinfunction "6_6") (pintype "passive"))
      (node (ref "T2") (pin "7") (pinfunction "7_7") (pintype "passive"))
    )
    (net (code "54") (name "Net-(TP2-G9)") (class "Default")
      (node (ref "C13") (pin "1") (pinfunction "1_1") (pintype "passive"))
      (node (ref "R15") (pin "1") (pinfunction "1_1") (pintype "passive"))
      (node (ref "R16") (pin "1") (pinfunction "1_1") (pintype "passive"))
      (node (ref "R7") (pin "1") (pinfunction "1_1") (pintype "passive"))
      (node (ref "TP2") (pin "1") (pinfunction "G9_1") (pintype "passive"))
      (node (ref "U1") (pin "2") (pinfunction "1IN-_2") (pintype "input"))
    )
    (net (code "55") (name "Net-(TP3-G9)") (class "Default")
      (node (ref "C19") (pin "1") (pinfunction "1_1") (pintype "passive"))
      (node (ref "R14") (pin "1") (pinfunction "1_1") (pintype "passive"))
      (node (ref "R5") (pin "2") (pinfunction "2_2") (pintype "passive"))
      (node (ref "TP3") (pin "1") (pinfunction "G9_1") (pintype "passive"))
      (node (ref "U1") (pin "16") (pinfunction "2IN+_16") (pintype "input"))
    )
    (net (code "56") (name "Net-(TP7-G9)") (class "Default")
      (node (ref "C16") (pin "2") (pinfunction "2_2") (pintype "passive"))
      (node (ref "R17") (pin "1") (pinfunction "1_1") (pintype "passive"))
      (node (ref "R18") (pin "1") (pinfunction "1_1") (pintype "passive"))
      (node (ref "R9") (pin "2") (pinfunction "2_2") (pintype "passive"))
      (node (ref "TP7") (pin "1") (pinfunction "G9_1") (pintype "passive"))
      (node (ref "U1") (pin "15") (pinfunction "2IN-_15") (pintype "input"))
      (node (ref "U2") (pin "1") (pinfunction "C_1") (pintype "passive"))
      (node (ref "U2") (pin "2") (pinfunction "REF_2") (pintype "passive"))
    )
    (net (code "57") (name "Net-(TP8-G9)") (class "Default")
      (node (ref "R13") (pin "1") (pinfunction "1_1") (pintype "passive"))
      (node (ref "TP8") (pin "1") (pinfunction "G9_1") (pintype "passive"))
      (node (ref "U1") (pin "6") (pinfunction "RT_6") (pintype "passive"))
    )
    (net (code "58") (name "Net-(TP12-G9)") (class "Default")
      (node (ref "C18") (pin "1") (pinfunction "1_1") (pintype "passive"))
      (node (ref "TP12") (pin "1") (pinfunction "G9_1") (pintype "passive"))
      (node (ref "U1") (pin "5") (pinfunction "CT_5") (pintype "passive"))
    )
    (net (code "59") (name "Net-(TP20-G9)") (class "Default")
      (node (ref "C34") (pin "1") (pinfunction "1_1") (pintype "passive"))
      (node (ref "R30") (pin "1") (pinfunction "1_1") (pintype "passive"))
      (node (ref "R41") (pin "1") (pinfunction "1_1") (pintype "passive"))
      (node (ref "R42") (pin "1") (pinfunction "1_1") (pintype "passive"))
      (node (ref "TP20") (pin "1") (pinfunction "G9_1") (pintype "passive"))
      (node (ref "U3") (pin "2") (pinfunction "1IN-_2") (pintype "input"))
    )
    (net (code "60") (name "Net-(TP21-G9)") (class "Default")
      (node (ref "C39") (pin "1") (pinfunction "1_1") (pintype "passive"))
      (node (ref "R29") (pin "2") (pinfunction "2_2") (pintype "passive"))
      (node (ref "R39") (pin "1") (pinfunction "1_1") (pintype "passive"))
      (node (ref "TP21") (pin "1") (pinfunction "G9_1") (pintype "passive"))
      (node (ref "U3") (pin "16") (pinfunction "2IN+_16") (pintype "input"))
    )
    (net (code "61") (name "Net-(TP26-G9)") (class "Default")
      (node (ref "C36") (pin "2") (pinfunction "2_2") (pintype "passive"))
      (node (ref "R32") (pin "2") (pinfunction "2_2") (pintype "passive"))
      (node (ref "R43") (pin "1") (pinfunction "1_1") (pintype "passive"))
      (node (ref "R44") (pin "1") (pinfunction "1_1") (pintype "passive"))
      (node (ref "TP26") (pin "1") (pinfunction "G9_1") (pintype "passive"))
      (node (ref "U3") (pin "15") (pinfunction "2IN-_15") (pintype "input"))
      (node (ref "U4") (pin "1") (pinfunction "C_1") (pintype "passive"))
      (node (ref "U4") (pin "2") (pinfunction "REF_2") (pintype "passive"))
    )
    (net (code "62") (name "Net-(TP28-G9)") (class "Default")
      (node (ref "R38") (pin "1") (pinfunction "1_1") (pintype "passive"))
      (node (ref "TP28") (pin "1") (pinfunction "G9_1") (pintype "passive"))
      (node (ref "U3") (pin "6") (pinfunction "RT_6") (pintype "passive"))
    )
    (net (code "63") (name "Net-(TP32-G9)") (class "Default")
      (node (ref "C38") (pin "1") (pinfunction "1_1") (pintype "passive"))
      (node (ref "TP32") (pin "1") (pinfunction "G9_1") (pintype "passive"))
      (node (ref "U3") (pin "5") (pinfunction "CT_5") (pintype "passive"))
    )
    (net (code "64") (name "Net-(U1-C1)") (class "Default")
      (node (ref "R8") (pin "1") (pinfunction "1_1") (pintype "passive"))
      (node (ref "U1") (pin "11") (pinfunction "C2_11") (pintype "passive"))
      (node (ref "U1") (pin "8") (pinfunction "C1_8") (pintype "passive"))
    )
    (net (code "65") (name "Net-(U1-DTC)") (class "Default")
      (node (ref "R19") (pin "2") (pinfunction "2_2") (pintype "passive"))
      (node (ref "U1") (pin "4") (pinfunction "DTC_4") (pintype "input"))
    )
    (net (code "66") (name "Net-(U3-C1)") (class "Default")
      (node (ref "R31") (pin "1") (pinfunction "1_1") (pintype "passive"))
      (node (ref "U3") (pin "11") (pinfunction "C2_11") (pintype "passive"))
      (node (ref "U3") (pin "8") (pinfunction "C1_8") (pintype "passive"))
    )
    (net (code "67") (name "Net-(U3-DTC)") (class "Default")
      (node (ref "R45") (pin "2") (pinfunction "2_2") (pintype "passive"))
      (node (ref "U3") (pin "4") (pinfunction "DTC_4") (pintype "input"))
    )
  )
)
